# Stm32.net
KiCad netlist of a schematic drawn in Altium Designer
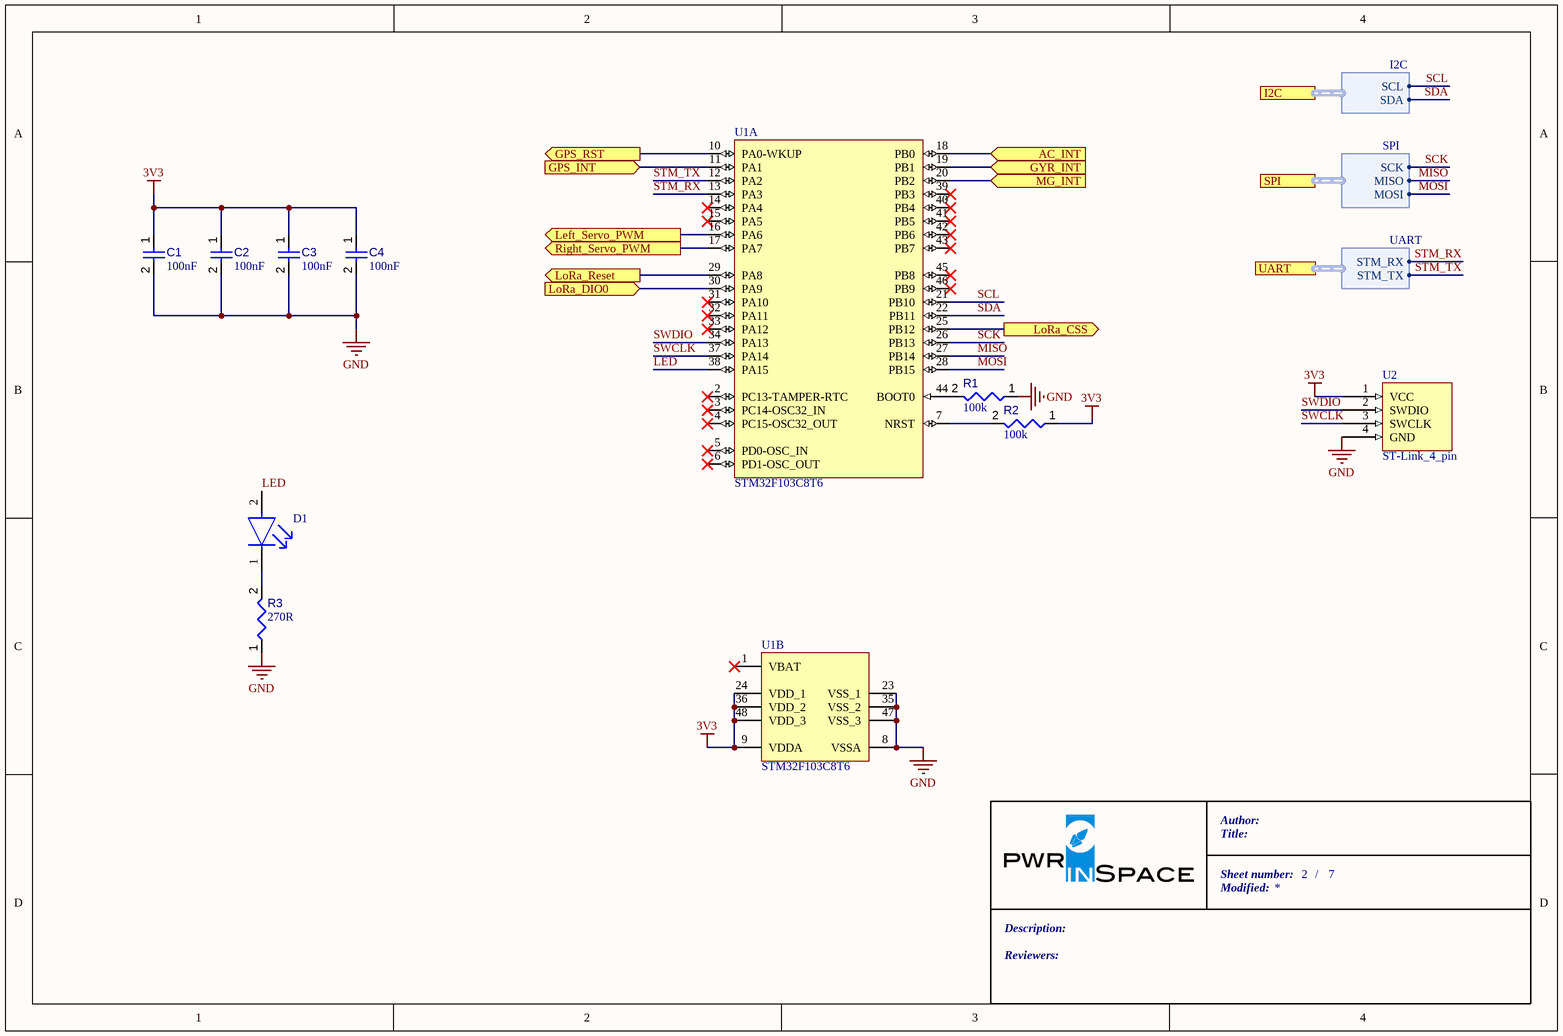
[diagram p0: Stm32.SchDoc]

(export (version "E")
  (design (tool "Eeschema 10.0.6"))
  (components
    (comp (ref "C1")
      (value "100nF")
      (footprint "CAPC0805(2012)145_L")
      (description "Chip Capacitor, 100µF +/-20%, 6.3V, 0805, Thickness 1.45 mm")
      (fields (field (name "TOLERANCE") "10%") (field (name "Comment") "Capacitor 100µF +/-20% 6.3V 0805"))
      (libsource (lib "PWr in Space team") (part "CAP-NP-2"))
    )
    (comp (ref "C2")
      (value "100nF")
      (footprint "CAPC0805(2012)145_L")
      (description "Chip Capacitor, 100µF +/-20%, 6.3V, 0805, Thickness 1.45 mm")
      (fields (field (name "TOLERANCE") "10%") (field (name "Comment") "Capacitor 100µF +/-20% 6.3V 0805"))
      (libsource (lib "PWr in Space team") (part "CAP-NP-2"))
    )
    (comp (ref "C3")
      (value "100nF")
      (footprint "CAPC0805(2012)145_L")
      (description "Chip Capacitor, 100µF +/-20%, 6.3V, 0805, Thickness 1.45 mm")
      (fields (field (name "TOLERANCE") "10%") (field (name "Comment") "Capacitor 100µF +/-20% 6.3V 0805"))
      (libsource (lib "PWr in Space team") (part "CAP-NP-2"))
    )
    (comp (ref "C4")
      (value "100nF")
      (footprint "CAPC0805(2012)145_L")
      (description "Chip Capacitor, 100µF +/-20%, 6.3V, 0805, Thickness 1.45 mm")
      (fields (field (name "TOLERANCE") "10%") (field (name "Comment") "Capacitor 100µF +/-20% 6.3V 0805"))
      (libsource (lib "PWr in Space team") (part "CAP-NP-2"))
    )
    (comp (ref "D1")
      (value "150080SS75000")
      (footprint "FP-150080SS75000-MFG")
      (description "Red 630nm LED Indication - Discrete 1.9V 0805 (2012 Metric)")
      (libsource (lib "PWr in Space team") (part "8706943c75ba83719d021d2fdc84c58"))
    )
    (comp (ref "R1")
      (value "100k")
      (footprint "RESC2013X50X35ML15T15")
      (description "Chip Resistor, 10 KOhm, +/- 1%, 125 mW, -55 to 155 degC, 0805 (2012 Metric)")
      (fields (field (name "TOLERANCE") "1%") (field (name "POWER") "125mW"))
      (libsource (lib "PWr in Space team") (part "RES-2"))
    )
    (comp (ref "R2")
      (value "100k")
      (footprint "RESC2013X50X35ML15T15")
      (description "Chip Resistor, 10 KOhm, +/- 1%, 125 mW, -55 to 155 degC, 0805 (2012 Metric)")
      (fields (field (name "TOLERANCE") "1%") (field (name "POWER") "125mW"))
      (libsource (lib "PWr in Space team") (part "RES-2"))
    )
    (comp (ref "R3")
      (value "270R")
      (footprint "RESC2013X50X35ML15T15")
      (description "Chip Resistor, 10 KOhm, +/- 1%, 125 mW, -55 to 155 degC, 0805 (2012 Metric)")
      (fields (field (name "TOLERANCE") "1%") (field (name "POWER") "125mW"))
      (libsource (lib "PWr in Space team") (part "RES-2"))
    )
    (comp (ref "U1")
      (value "STM32F103C8T6")
      (footprint "STM-LQFP48_M")
      (description "IC MCU 32BIT 64KB FLASH 48LQFP")
      (libsource (lib "PWr in Space team") (part "MC-ARM-STM32F103X8_B-SQ48"))
    )
    (comp (ref "U2")
      (value "ST-Link_4_pin")
      (footprint "ST-Link_4_pin-Footprint-1")
      (description "ST-Link 4 pin DEBUG (3V3, SWDIO, SWCLK, GND)")
      (libsource (lib "PWr in Space team") (part "ST-Link_4_pin-Symbol-1"))
    )
  )
  (nets
    (net (code "4") (name "/AC_INT") (class "Default")
      (node (ref "U1") (pin "18") (pinfunction "PB0_18") (pintype "bidirectional"))
    )
    (net (code "5") (name "/GPS_INT") (class "Default")
      (node (ref "U1") (pin "11") (pinfunction "PA1_11") (pintype "bidirectional"))
    )
    (net (code "6") (name "/GPS_RST") (class "Default")
      (node (ref "U1") (pin "10") (pinfunction "PA0-WKUP_10") (pintype "bidirectional"))
    )
    (net (code "7") (name "/GYR_INT") (class "Default")
      (node (ref "U1") (pin "19") (pinfunction "PB1_19") (pintype "bidirectional"))
    )
    (net (code "8") (name "/LED") (class "Default")
      (node (ref "D1") (pin "2") (pinfunction "A_2") (pintype "passive"))
      (node (ref "U1") (pin "38") (pinfunction "PA15_38") (pintype "bidirectional"))
    )
    (net (code "9") (name "/Left_Servo_PWM") (class "Default")
      (node (ref "U1") (pin "16") (pinfunction "PA6_16") (pintype "bidirectional"))
    )
    (net (code "10") (name "/LoRa_CSS") (class "Default")
      (node (ref "U1") (pin "25") (pinfunction "PB12_25") (pintype "bidirectional"))
    )
    (net (code "11") (name "/LoRa_DIO0") (class "Default")
      (node (ref "U1") (pin "30") (pinfunction "PA9_30") (pintype "bidirectional"))
    )
    (net (code "12") (name "/LoRa_Reset") (class "Default")
      (node (ref "U1") (pin "29") (pinfunction "PA8_29") (pintype "bidirectional"))
    )
    (net (code "13") (name "/MG_INT") (class "Default")
      (node (ref "U1") (pin "20") (pinfunction "PB2_20") (pintype "bidirectional"))
    )
    (net (code "14") (name "/MISO") (class "Default")
      (node (ref "U1") (pin "27") (pinfunction "PB14_27") (pintype "bidirectional"))
    )
    (net (code "15") (name "/MOSI") (class "Default")
      (node (ref "U1") (pin "28") (pinfunction "PB15_28") (pintype "bidirectional"))
    )
    (net (code "16") (name "/Right_Servo_PWM") (class "Default")
      (node (ref "U1") (pin "17") (pinfunction "PA7_17") (pintype "bidirectional"))
    )
    (net (code "17") (name "/SCK") (class "Default")
      (node (ref "U1") (pin "26") (pinfunction "PB13_26") (pintype "bidirectional"))
    )
    (net (code "18") (name "/SCL") (class "Default")
      (node (ref "U1") (pin "21") (pinfunction "PB10_21") (pintype "bidirectional"))
    )
    (net (code "19") (name "/SDA") (class "Default")
      (node (ref "U1") (pin "22") (pinfunction "PB11_22") (pintype "bidirectional"))
    )
    (net (code "20") (name "/STM_RX") (class "Default")
      (node (ref "U1") (pin "13") (pinfunction "PA3_13") (pintype "bidirectional"))
    )
    (net (code "21") (name "/STM_TX") (class "Default")
      (node (ref "U1") (pin "12") (pinfunction "PA2_12") (pintype "bidirectional"))
    )
    (net (code "22") (name "/SWCLK") (class "Default")
      (node (ref "U1") (pin "37") (pinfunction "PA14_37") (pintype "bidirectional"))
      (node (ref "U2") (pin "3") (pinfunction "SWCLK_3") (pintype "input"))
    )
    (net (code "23") (name "/SWDIO") (class "Default")
      (node (ref "U1") (pin "34") (pinfunction "PA13_34") (pintype "bidirectional"))
      (node (ref "U2") (pin "2") (pinfunction "SWDIO_2") (pintype "input"))
    )
    (net (code "27") (name "3V3") (class "Default")
      (node (ref "C1") (pin "1") (pinfunction "1_1") (pintype "passive"))
      (node (ref "C2") (pin "1") (pinfunction "1_1") (pintype "passive"))
      (node (ref "C3") (pin "1") (pinfunction "1_1") (pintype "passive"))
      (node (ref "C4") (pin "1") (pinfunction "1_1") (pintype "passive"))
      (node (ref "R2") (pin "1") (pinfunction "1_1") (pintype "passive"))
      (node (ref "U1") (pin "24") (pinfunction "VDD_1_24") (pintype "power_in"))
      (node (ref "U1") (pin "36") (pinfunction "VDD_2_36") (pintype "power_in"))
      (node (ref "U1") (pin "48") (pinfunction "VDD_3_48") (pintype "power_in"))
      (node (ref "U1") (pin "9") (pinfunction "VDDA_9") (pintype "power_in"))
      (node (ref "U2") (pin "1") (pinfunction "VCC_1") (pintype "input"))
    )
    (net (code "28") (name "GND") (class "Default")
      (node (ref "C1") (pin "2") (pinfunction "2_2") (pintype "passive"))
      (node (ref "C2") (pin "2") (pinfunction "2_2") (pintype "passive"))
      (node (ref "C3") (pin "2") (pinfunction "2_2") (pintype "passive"))
      (node (ref "C4") (pin "2") (pinfunction "2_2") (pintype "passive"))
      (node (ref "R1") (pin "1") (pinfunction "1_1") (pintype "passive"))
      (node (ref "R3") (pin "1") (pinfunction "1_1") (pintype "passive"))
      (node (ref "U1") (pin "23") (pinfunction "VSS_1_23") (pintype "power_in"))
      (node (ref "U1") (pin "35") (pinfunction "VSS_2_35") (pintype "power_in"))
      (node (ref "U1") (pin "47") (pinfunction "VSS_3_47") (pintype "power_in"))
      (node (ref "U1") (pin "8") (pinfunction "VSSA_8") (pintype "power_in"))
      (node (ref "U2") (pin "4") (pinfunction "GND_4") (pintype "input"))
    )
    (net (code "29") (name "Net-(D1-C)") (class "Default")
      (node (ref "D1") (pin "1") (pinfunction "C_1") (pintype "passive"))
      (node (ref "R3") (pin "2") (pinfunction "2_2") (pintype "passive"))
    )
    (net (code "30") (name "Net-(U1A-BOOT0)") (class "Default")
      (node (ref "R1") (pin "2") (pinfunction "2_2") (pintype "passive"))
      (node (ref "U1") (pin "44") (pinfunction "BOOT0_44") (pintype "input"))
    )
    (net (code "31") (name "Net-(U1A-NRST)") (class "Default")
      (node (ref "R2") (pin "2") (pinfunction "2_2") (pintype "passive"))
      (node (ref "U1") (pin "7") (pinfunction "NRST_7") (pintype "bidirectional"))
    )
    (net (code "32") (name "unconnected-(U1A-PA4-Pad14)") (class "Default")
      (node (ref "U1") (pin "14") (pinfunction "PA4_14") (pintype "bidirectional+no_connect"))
    )
    (net (code "33") (name "unconnected-(U1A-PA5-Pad15)") (class "Default")
      (node (ref "U1") (pin "15") (pinfunction "PA5_15") (pintype "bidirectional+no_connect"))
    )
    (net (code "34") (name "unconnected-(U1A-PA10-Pad31)") (class "Default")
      (node (ref "U1") (pin "31") (pinfunction "PA10_31") (pintype "bidirectional+no_connect"))
    )
    (net (code "35") (name "unconnected-(U1A-PA11-Pad32)") (class "Default")
      (node (ref "U1") (pin "32") (pinfunction "PA11_32") (pintype "bidirectional+no_connect"))
    )
    (net (code "36") (name "unconnected-(U1A-PA12-Pad33)") (class "Default")
      (node (ref "U1") (pin "33") (pinfunction "PA12_33") (pintype "bidirectional+no_connect"))
    )
    (net (code "37") (name "unconnected-(U1A-PB3-Pad39)") (class "Default")
      (node (ref "U1") (pin "39") (pinfunction "PB3_39") (pintype "bidirectional+no_connect"))
    )
    (net (code "38") (name "unconnected-(U1A-PB4-Pad40)") (class "Default")
      (node (ref "U1") (pin "40") (pinfunction "PB4_40") (pintype "bidirectional+no_connect"))
    )
    (net (code "39") (name "unconnected-(U1A-PB5-Pad41)") (class "Default")
      (node (ref "U1") (pin "41") (pinfunction "PB5_41") (pintype "bidirectional+no_connect"))
    )
    (net (code "40") (name "unconnected-(U1A-PB6-Pad42)") (class "Default")
      (node (ref "U1") (pin "42") (pinfunction "PB6_42") (pintype "bidirectional+no_connect"))
    )
    (net (code "41") (name "unconnected-(U1A-PB7-Pad43)") (class "Default")
      (node (ref "U1") (pin "43") (pinfunction "PB7_43") (pintype "bidirectional+no_connect"))
    )
    (net (code "42") (name "unconnected-(U1A-PB8-Pad45)") (class "Default")
      (node (ref "U1") (pin "45") (pinfunction "PB8_45") (pintype "bidirectional+no_connect"))
    )
    (net (code "43") (name "unconnected-(U1A-PB9-Pad46)") (class "Default")
      (node (ref "U1") (pin "46") (pinfunction "PB9_46") (pintype "bidirectional+no_connect"))
    )
    (net (code "44") (name "unconnected-(U1A-PC13-TAMPER-RTC-Pad2)") (class "Default")
      (node (ref "U1") (pin "2") (pinfunction "PC13-TAMPER-RTC_2") (pintype "bidirectional+no_connect"))
    )
    (net (code "45") (name "unconnected-(U1A-PC14-OSC32_IN-Pad3)") (class "Default")
      (node (ref "U1") (pin "3") (pinfunction "PC14-OSC32_IN_3") (pintype "bidirectional+no_connect"))
    )
    (net (code "46") (name "unconnected-(U1A-PC15-OSC32_OUT-Pad4)") (class "Default")
      (node (ref "U1") (pin "4") (pinfunction "PC15-OSC32_OUT_4") (pintype "bidirectional+no_connect"))
    )
    (net (code "47") (name "unconnected-(U1A-PD0-OSC_IN-Pad5)") (class "Default")
      (node (ref "U1") (pin "5") (pinfunction "PD0-OSC_IN_5") (pintype "bidirectional+no_connect"))
    )
    (net (code "48") (name "unconnected-(U1A-PD1-OSC_OUT-Pad6)") (class "Default")
      (node (ref "U1") (pin "6") (pinfunction "PD1-OSC_OUT_6") (pintype "bidirectional+no_connect"))
    )
    (net (code "49") (name "unconnected-(U1B-VBAT-Pad1)") (class "Default")
      (node (ref "U1") (pin "1") (pinfunction "VBAT_1") (pintype "power_in+no_connect"))
    )
  )
)
